# p_key.net
KiCad netlist of a schematic drawn in EAGLE
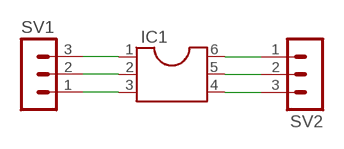
[diagram p0: schematic, sheet 1]

(export (version "E")
  (design (tool "Eeschema 10.0.6"))
  (components
    (comp (ref "IC1")
      (value "DIL6")
      (footprint "eagle-import:DIL06")
      (libsource (lib "eagle-import") (part "DIL6"))
    )
    (comp (ref "SV1")
      (value "MA03-1")
      (footprint "eagle-import:MA03-1")
      (libsource (lib "eagle-import") (part "MA03-1"))
    )
    (comp (ref "SV2")
      (value "MA03-1")
      (footprint "eagle-import:MA03-1")
      (libsource (lib "eagle-import") (part "MA03-1"))
    )
  )
  (nets
    (net (code "1") (name "Net-(IC1-Pad1)") (class "Default")
      (node (ref "IC1") (pin "1") (pinfunction "1_1") (pintype "passive"))
      (node (ref "SV1") (pin "3") (pinfunction "3_3") (pintype "passive"))
    )
    (net (code "2") (name "Net-(IC1-Pad2)") (class "Default")
      (node (ref "IC1") (pin "2") (pinfunction "2_2") (pintype "passive"))
      (node (ref "SV1") (pin "2") (pinfunction "2_2") (pintype "passive"))
    )
    (net (code "3") (name "Net-(IC1-Pad3)") (class "Default")
      (node (ref "IC1") (pin "3") (pinfunction "3_3") (pintype "passive"))
      (node (ref "SV1") (pin "1") (pinfunction "1_1") (pintype "passive"))
    )
    (net (code "4") (name "Net-(IC1-Pad4)") (class "Default")
      (node (ref "IC1") (pin "4") (pinfunction "4_4") (pintype "passive"))
      (node (ref "SV2") (pin "3") (pinfunction "3_3") (pintype "passive"))
    )
    (net (code "5") (name "Net-(IC1-Pad5)") (class "Default")
      (node (ref "IC1") (pin "5") (pinfunction "5_5") (pintype "passive"))
      (node (ref "SV2") (pin "2") (pinfunction "2_2") (pintype "passive"))
    )
    (net (code "6") (name "Net-(IC1-Pad6)") (class "Default")
      (node (ref "IC1") (pin "6") (pinfunction "6_6") (pintype "passive"))
      (node (ref "SV2") (pin "1") (pinfunction "1_1") (pintype "passive"))
    )
  )
)
